# ST_LINK_V2-1_2.net
KiCad netlist of a schematic drawn in Altium Designer
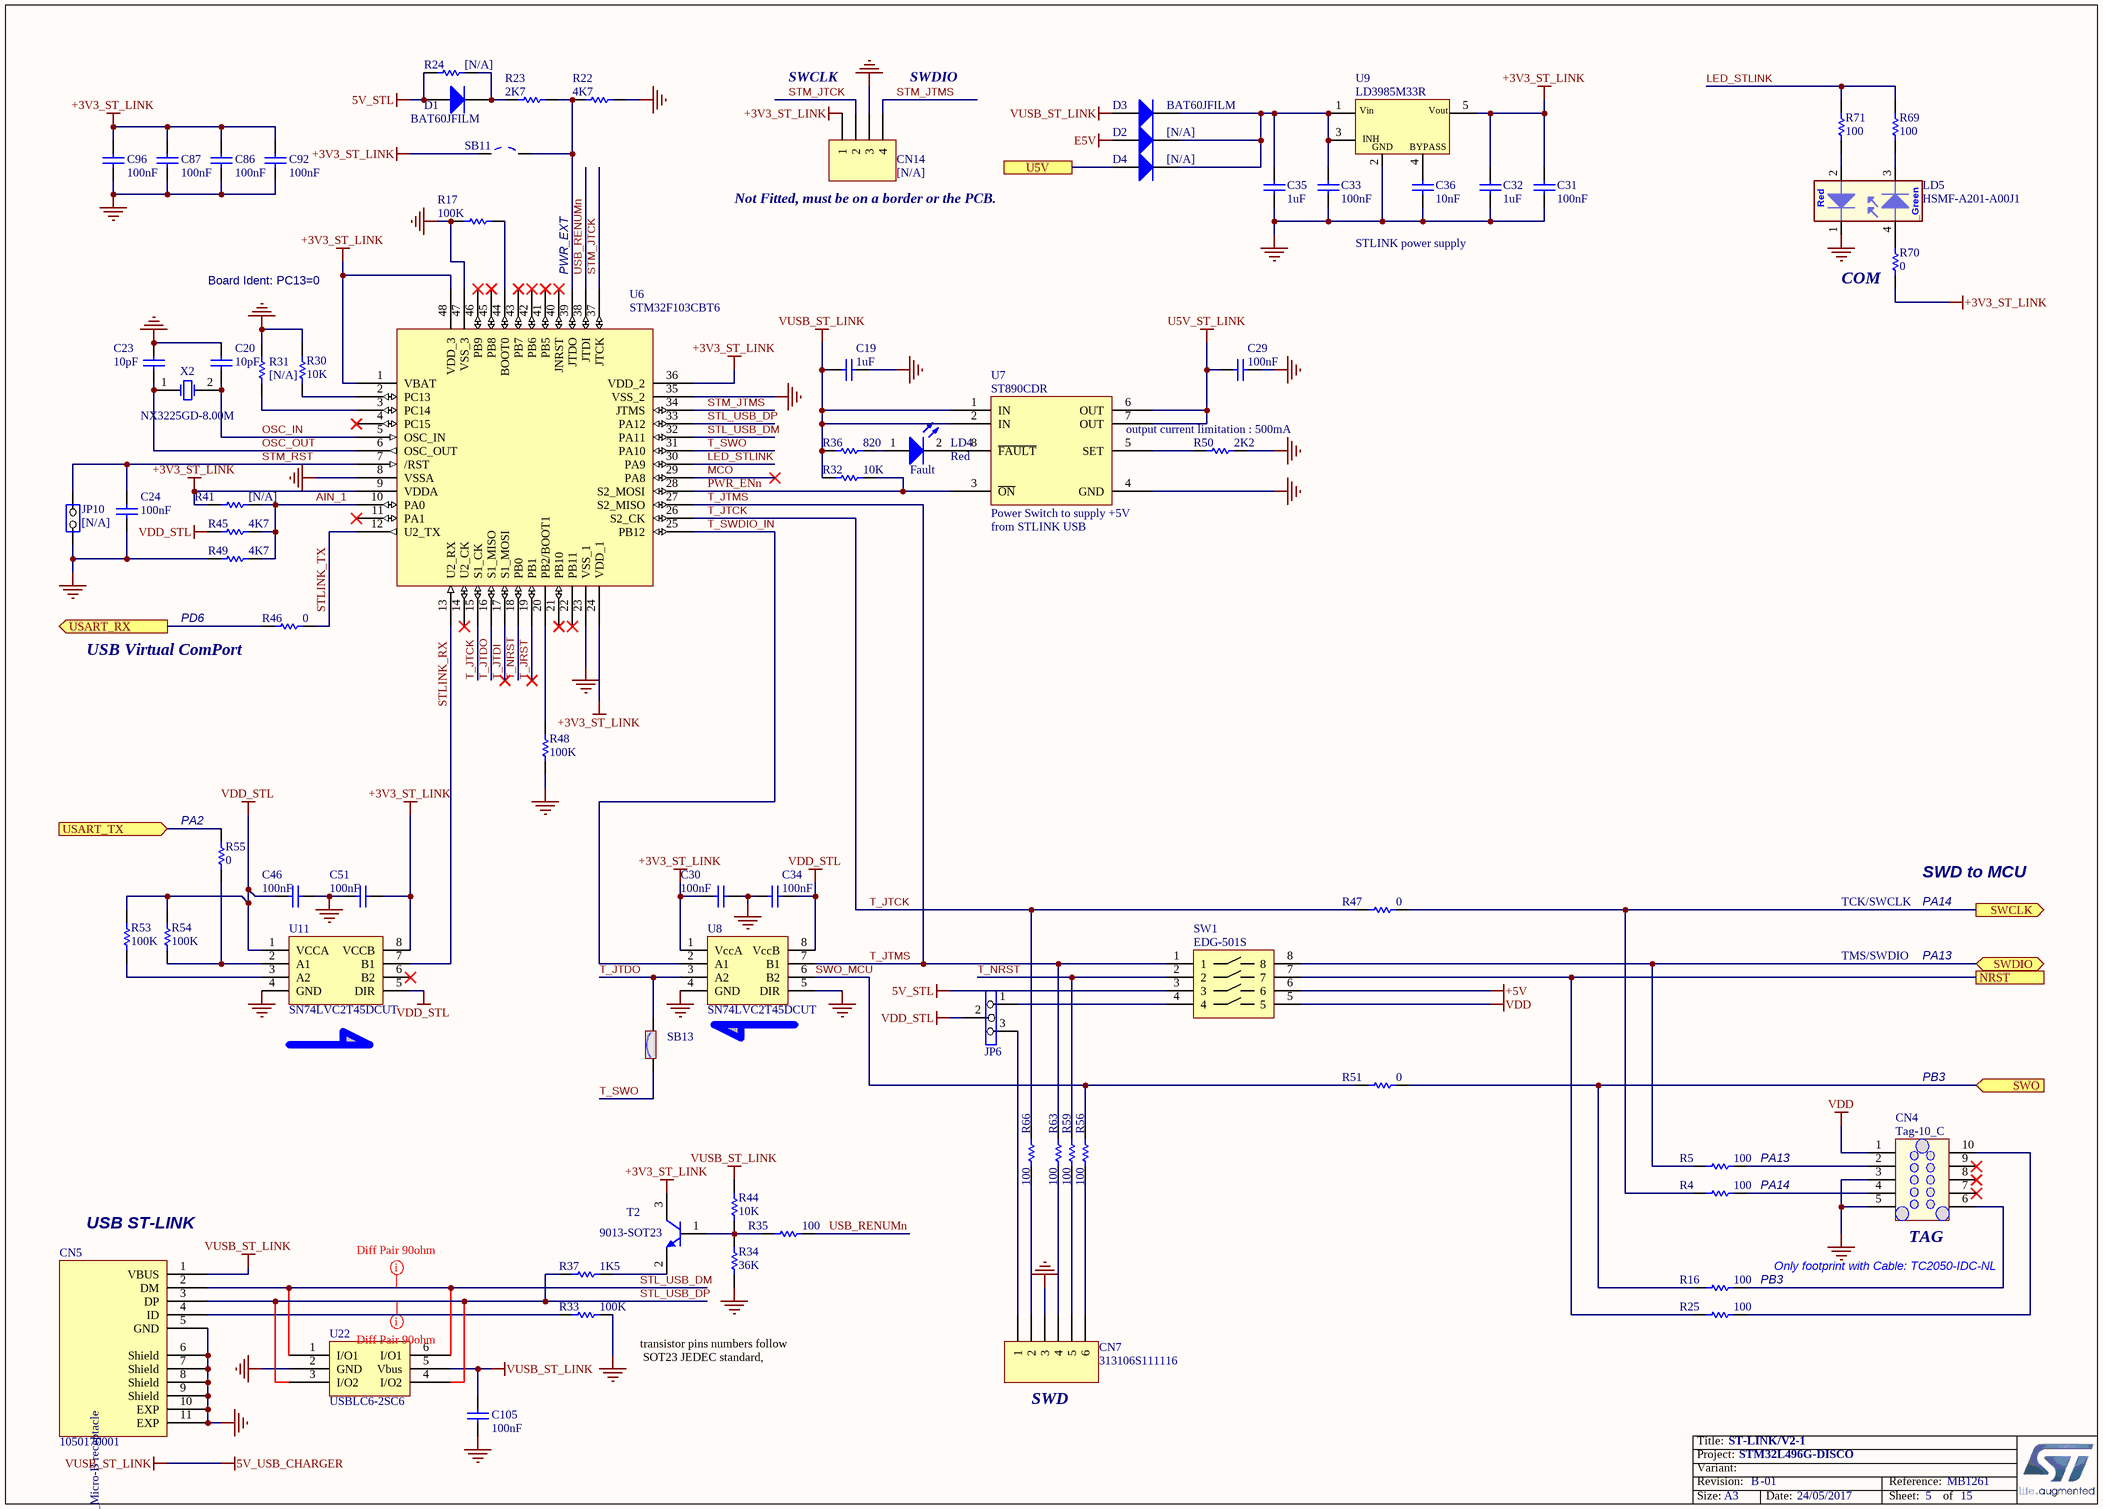
[diagram p0: ST_LINK_V2-1_2.SCHDOC]

(export (version "E")
  (design (tool "Eeschema 10.0.6"))
  (components
    (comp (ref "C19")
      (value "1uF")
      (footprint "0603C")
      (description "Capacitor,1uF,0603,16V,10%,X5R,YAGEO")
      (fields (field (name "Comment") "CC0603KRX5R7BB105") (field (name "PUBLISHER") "Altium Limited"))
      (libsource (lib "Miscellaneous Devices") (part "Cap"))
    )
    (comp (ref "C20")
      (value "10pF")
      (footprint "0603C")
      (description "Capacitor,10pF,5%,50V,NPO,0603,YAGEO")
      (fields (field (name "Comment") "CC0603JRNPO9BN100") (field (name "PUBLISHER") "Altium Limited"))
      (libsource (lib "Miscellaneous Devices") (part "Cap"))
    )
    (comp (ref "C23")
      (value "10pF")
      (footprint "0603C")
      (description "Capacitor,10pF,5%,50V,NPO,0603,YAGEO")
      (fields (field (name "Comment") "CC0603JRNPO9BN100") (field (name "PUBLISHER") "Altium Limited"))
      (libsource (lib "Miscellaneous Devices") (part "Cap"))
    )
    (comp (ref "C24")
      (value "100nF")
      (footprint "0603C")
      (description "Capacitor,100nF,10%,16V,X7R,0603,YAGEO")
      (fields (field (name "Comment") "CC0603KRX7R7BB104") (field (name "PUBLISHER") "Altium Limited"))
      (libsource (lib "Miscellaneous Devices") (part "Cap"))
    )
    (comp (ref "C29")
      (value "100nF")
      (footprint "0603C")
      (description "Capacitor,100nF,10%,16V,X7R,0603,YAGEO")
      (fields (field (name "Comment") "CC0603KRX7R7BB104") (field (name "PUBLISHER") "Altium Limited"))
      (libsource (lib "Miscellaneous Devices") (part "Cap"))
    )
    (comp (ref "C30")
      (value "100nF")
      (footprint "0603C")
      (description "Capacitor,100nF,10%,16V,X7R,0603,YAGEO")
      (fields (field (name "Comment") "CC0603KRX7R7BB104") (field (name "PUBLISHER") "Altium Limited"))
      (libsource (lib "Miscellaneous Devices") (part "Cap"))
    )
    (comp (ref "C31")
      (value "100nF")
      (footprint "0603C")
      (description "Capacitor,100nF,10%,16V,X7R,0603,YAGEO")
      (fields (field (name "Comment") "CC0603KRX7R7BB104") (field (name "PUBLISHER") "Altium Limited"))
      (libsource (lib "Miscellaneous Devices") (part "Cap"))
    )
    (comp (ref "C32")
      (value "1uF")
      (footprint "0603C")
      (description "Capacitor,1uF,0603,16V,10%,X5R,YAGEO")
      (fields (field (name "Comment") "CC0603KRX5R7BB105") (field (name "PUBLISHER") "Altium Limited"))
      (libsource (lib "Miscellaneous Devices") (part "Cap"))
    )
    (comp (ref "C33")
      (value "100nF")
      (footprint "0603C")
      (description "Capacitor,100nF,10%,16V,X7R,0603,YAGEO")
      (fields (field (name "Comment") "CC0603KRX7R7BB104") (field (name "PUBLISHER") "Altium Limited"))
      (libsource (lib "Miscellaneous Devices") (part "Cap"))
    )
    (comp (ref "C34")
      (value "100nF")
      (footprint "0603C")
      (description "Capacitor,100nF,10%,16V,X7R,0603,YAGEO")
      (fields (field (name "Comment") "CC0603KRX7R7BB104") (field (name "PUBLISHER") "Altium Limited"))
      (libsource (lib "Miscellaneous Devices") (part "Cap"))
    )
    (comp (ref "C35")
      (value "1uF")
      (footprint "0603C")
      (description "Capacitor,1uF,0603,16V,10%,X5R,YAGEO")
      (fields (field (name "Comment") "CC0603KRX5R7BB105") (field (name "PUBLISHER") "Altium Limited"))
      (libsource (lib "Miscellaneous Devices") (part "Cap"))
    )
    (comp (ref "C36")
      (value "10nF")
      (footprint "0603C")
      (description "Capacitor,10nF,0603,50V,10%,X7R,YAGEO;")
      (fields (field (name "Comment") "CC0603KRX7R9BB103") (field (name "PUBLISHER") "Altium Limited"))
      (libsource (lib "Miscellaneous Devices") (part "Cap"))
    )
    (comp (ref "C46")
      (value "100nF")
      (footprint "0603C")
      (description "Capacitor,100nF,10%,16V,X7R,0603,YAGEO")
      (fields (field (name "Comment") "CC0603KRX7R7BB104") (field (name "PUBLISHER") "Altium Limited"))
      (libsource (lib "Miscellaneous Devices") (part "Cap"))
    )
    (comp (ref "C51")
      (value "100nF")
      (footprint "0603C")
      (description "Capacitor,100nF,10%,16V,X7R,0603,YAGEO")
      (fields (field (name "Comment") "CC0603KRX7R7BB104") (field (name "PUBLISHER") "Altium Limited"))
      (libsource (lib "Miscellaneous Devices") (part "Cap"))
    )
    (comp (ref "C86")
      (value "100nF")
      (footprint "0603C")
      (description "Capacitor,100nF,10%,16V,X7R,0603,YAGEO")
      (fields (field (name "Comment") "CC0603KRX7R7BB104") (field (name "PUBLISHER") "Altium Limited"))
      (libsource (lib "Miscellaneous Devices") (part "Cap"))
    )
    (comp (ref "C87")
      (value "100nF")
      (footprint "0603C")
      (description "Capacitor,100nF,10%,16V,X7R,0603,YAGEO")
      (fields (field (name "Comment") "CC0603KRX7R7BB104") (field (name "PUBLISHER") "Altium Limited"))
      (libsource (lib "Miscellaneous Devices") (part "Cap"))
    )
    (comp (ref "C92")
      (value "100nF")
      (footprint "0603C")
      (description "Capacitor,100nF,10%,16V,X7R,0603,YAGEO")
      (fields (field (name "Comment") "CC0603KRX7R7BB104") (field (name "PUBLISHER") "Altium Limited"))
      (libsource (lib "Miscellaneous Devices") (part "Cap"))
    )
    (comp (ref "C96")
      (value "100nF")
      (footprint "0603C")
      (description "Capacitor,100nF,10%,16V,X7R,0603,YAGEO")
      (fields (field (name "Comment") "CC0603KRX7R7BB104") (field (name "PUBLISHER") "Altium Limited"))
      (libsource (lib "Miscellaneous Devices") (part "Cap"))
    )
    (comp (ref "C105")
      (value "100nF")
      (footprint "0603C")
      (description "Capacitor,100nF,10%,16V,X7R,0603,YAGEO")
      (fields (field (name "Comment") "CC0603KRX7R7BB104") (field (name "PUBLISHER") "Altium Limited"))
      (libsource (lib "Miscellaneous Devices") (part "Cap"))
    )
    (comp (ref "CN4")
      (value "Tag-10_C")
      (footprint "TC2050-IDC-NL")
      (description "Footprint for TC2050-IDC-430 plug of nails (TM) cable for MP430")
      (libsource (lib "MCD_TOOLS_CONNECTOR") (part "Tag-10_C"))
    )
    (comp (ref "CN5")
      (value "1050170001")
      (footprint "MICRO_USB_B_105017")
      (libsource (lib "Smartphone_accessory") (part "1050170001"))
    )
    (comp (ref "CN7")
      (value "313106S111116")
      (footprint "HDR_1X6_2R54_W")
      (description "Header, 6-Pin")
      (fields (field (name "PUBLISHER") "Altium Limited"))
      (libsource (lib "Miscellaneous Connectors") (part "Header 6"))
    )
    (comp (ref "CN14")
      (value "[N/A]")
      (footprint "HDR_1X4_2R54")
      (description "Header, 4-Pin")
      (fields (field (name "PUBLISHER") "Altium Limited"))
      (libsource (lib "MCD_TOOLS_CONNECTOR") (part "Header 4"))
    )
    (comp (ref "D1")
      (value "BAT60JFILM")
      (footprint "SOD-323")
      (fields (field (name "PROVIDED") "STM"))
      (libsource (lib "MCD_TOOLS") (part "BAT60JFILM"))
    )
    (comp (ref "D2")
      (value "[N/A]")
      (footprint "SOD-323")
      (description "BAT60JFILM")
      (fields (field (name "PROVIDED") "STM"))
      (libsource (lib "MCD_TOOLS") (part "BAT60JFILM"))
    )
    (comp (ref "D3")
      (value "BAT60JFILM")
      (footprint "SOD-323")
      (fields (field (name "PROVIDED") "STM"))
      (libsource (lib "MCD_TOOLS") (part "BAT60JFILM"))
    )
    (comp (ref "D4")
      (value "[N/A]")
      (footprint "SOD-323")
      (description "BAT60JFILM")
      (fields (field (name "PROVIDED") "STM"))
      (libsource (lib "MCD_TOOLS") (part "BAT60JFILM"))
    )
    (comp (ref "JP6")
      (value "3 PIN Jumper")
      (footprint "SIP3")
      (libsource (lib "STR910_SCHLIB") (part "Jumper3"))
    )
    (comp (ref "JP10") (value "[N/A]") (footprint "SIP2") (libsource (lib "*") (part "JP2")))
    (comp (ref "LD4")
      (value "19-217/R6C-AL1M2VY/3T")
      (footprint "0603D")
      (description "LED, Red ,0603")
      (fields
        (field (name "SILKSCREEN") "Fault")
        (field (name "CORLOR") "Red")
        (field (name "PUBLISHER") "Altium Limited")
      )
      (libsource (lib "Miscellaneous Devices") (part "LED2"))
    )
    (comp (ref "LD5")
      (value "HSMF-A201-A00J1")
      (footprint "LED2_3528")
      (description "Bicolor Led")
      (libsource (lib "MCD_TOOLS") (part "LD_BICOLOR_CMS"))
    )
    (comp (ref "R4")
      (value "100")
      (footprint "0603R")
      (description "Resistor, 100 ,0603,1%,YAGEO")
      (fields (field (name "Comment") "RC0603JR-07100RL") (field (name "PUBLISHER") "Altium Limited"))
      (libsource (lib "Miscellaneous Devices") (part "res1"))
    )
    (comp (ref "R5")
      (value "100")
      (footprint "0603R")
      (description "Resistor, 100 ,0603,1%,YAGEO")
      (fields (field (name "Comment") "RC0603JR-07100RL") (field (name "PUBLISHER") "Altium Limited"))
      (libsource (lib "Miscellaneous Devices") (part "res1"))
    )
    (comp (ref "R16")
      (value "100")
      (footprint "0603R")
      (description "Resistor, 100 ,0603,1%,YAGEO")
      (fields (field (name "Comment") "RC0603JR-07100RL") (field (name "PUBLISHER") "Altium Limited"))
      (libsource (lib "Miscellaneous Devices") (part "res1"))
    )
    (comp (ref "R17")
      (value "100K")
      (footprint "0603R")
      (description "Resistor,100K,0603,1%,YAGEO")
      (fields (field (name "Comment") "RC0603FR-07100KL") (field (name "PUBLISHER") "Altium Limited"))
      (libsource (lib "Miscellaneous Devices") (part "res1"))
    )
    (comp (ref "R22")
      (value "4K7")
      (footprint "0603R")
      (description "Resistor,4.7K,0603,1%,YAGEO")
      (fields (field (name "Comment") "RC0603FR-074K7L") (field (name "PUBLISHER") "Altium Limited"))
      (libsource (lib "Miscellaneous Devices") (part "res1"))
    )
    (comp (ref "R23")
      (value "2K7")
      (footprint "0603R")
      (description "Resistor,2.7K,0603,1%,YAGEO")
      (fields (field (name "Comment") "RC0603FR-072K7L") (field (name "PUBLISHER") "Altium Limited"))
      (libsource (lib "Miscellaneous Devices") (part "res1"))
    )
    (comp (ref "R24")
      (value "[N/A]")
      (footprint "0603R")
      (description "Resistor,0,0603,5%,YAGEO")
      (libsource (lib "MCD_TOOLS") (part "Res_0_5%_0402"))
    )
    (comp (ref "R25")
      (value "100")
      (footprint "0603R")
      (description "Resistor, 100 ,0603,1%,YAGEO")
      (fields (field (name "Comment") "RC0603JR-07100RL") (field (name "PUBLISHER") "Altium Limited"))
      (libsource (lib "Miscellaneous Devices") (part "res1"))
    )
    (comp (ref "R30")
      (value "10K")
      (footprint "0603R")
      (description "Resistor,10K,0603,1%,YAGEO")
      (fields (field (name "Comment") "RC0603FR-0710KL") (field (name "PUBLISHER") "Altium Limited"))
      (libsource (lib "Miscellaneous Devices") (part "res1"))
    )
    (comp (ref "R31")
      (value "[N/A]")
      (footprint "0603R")
      (description "Resistor,100K,0603,1%,YAGEO")
      (fields (field (name "PUBLISHER") "Altium Limited"))
      (libsource (lib "Miscellaneous Devices") (part "res1"))
    )
    (comp (ref "R32")
      (value "10K")
      (footprint "0603R")
      (description "Resistor,10K,0603,1%,YAGEO")
      (fields (field (name "Comment") "RC0603FR-0710KL") (field (name "PUBLISHER") "Altium Limited"))
      (libsource (lib "Miscellaneous Devices") (part "res1"))
    )
    (comp (ref "R33")
      (value "100K")
      (footprint "0603R")
      (description "Resistor,100K,0603,1%,YAGEO")
      (fields (field (name "Comment") "RC0603FR-07100KL") (field (name "PUBLISHER") "Altium Limited"))
      (libsource (lib "Miscellaneous Devices") (part "res1"))
    )
    (comp (ref "R34")
      (value "36K")
      (footprint "0603R")
      (description "Resistor,36K,0603,1%,YAGEO")
      (fields (field (name "Comment") "RC0603FR-0736KL") (field (name "PUBLISHER") "Altium Limited"))
      (libsource (lib "Miscellaneous Devices") (part "res1"))
    )
    (comp (ref "R35")
      (value "100")
      (footprint "0603R")
      (description "Resistor, 100 ,0603,1%,YAGEO")
      (fields (field (name "Comment") "RC0603JR-07100RL") (field (name "PUBLISHER") "Altium Limited"))
      (libsource (lib "Miscellaneous Devices") (part "res1"))
    )
    (comp (ref "R36")
      (value "820")
      (footprint "0603R")
      (description "Resistor")
      (fields (field (name "PUBLISHER") "Altium Limited"))
      (libsource (lib "Miscellaneous Devices") (part "res1"))
    )
    (comp (ref "R37")
      (value "1K5")
      (footprint "0603R")
      (description "Resistor,1.5K,0603,1%,YAGEO")
      (fields (field (name "Comment") "RC0603FR-071K5L") (field (name "PUBLISHER") "Altium Limited"))
      (libsource (lib "Miscellaneous Devices") (part "res1"))
    )
    (comp (ref "R41")
      (value "[N/A]")
      (footprint "0603R")
      (description "Resistor,100K,0603,1%,YAGEO")
      (fields (field (name "PUBLISHER") "Altium Limited"))
      (libsource (lib "Miscellaneous Devices") (part "res1"))
    )
    (comp (ref "R44")
      (value "10K")
      (footprint "0603R")
      (description "Resistor,10K,0603,1%,YAGEO")
      (fields (field (name "Comment") "RC0603FR-0710KL") (field (name "PUBLISHER") "Altium Limited"))
      (libsource (lib "Miscellaneous Devices") (part "res1"))
    )
    (comp (ref "R45")
      (value "4K7")
      (footprint "0603R")
      (description "Resistor,4.7K,0603,1%,YAGEO")
      (fields (field (name "Comment") "RC0603FR-074K7L") (field (name "PUBLISHER") "Altium Limited"))
      (libsource (lib "Miscellaneous Devices") (part "res1"))
    )
    (comp (ref "R46")
      (value "0")
      (footprint "0603R")
      (description "Resistor, 0 ,0603,1%,YAGEO")
      (fields (field (name "Comment") "RC0603JR-070RL") (field (name "PUBLISHER") "Altium Limited"))
      (libsource (lib "Miscellaneous Devices") (part "res1"))
    )
    (comp (ref "R47")
      (value "0")
      (footprint "0603R")
      (description "Resistor, 0 ,0603,1%,YAGEO")
      (fields (field (name "Comment") "RC0603JR-070RL") (field (name "PUBLISHER") "Altium Limited"))
      (libsource (lib "Miscellaneous Devices") (part "res1"))
    )
    (comp (ref "R48")
      (value "100K")
      (footprint "0603R")
      (description "Resistor,100K,0603,1%,YAGEO")
      (fields (field (name "Comment") "RC0603FR-07100KL") (field (name "PUBLISHER") "Altium Limited"))
      (libsource (lib "Miscellaneous Devices") (part "res1"))
    )
    (comp (ref "R49")
      (value "4K7")
      (footprint "0603R")
      (description "Resistor,4.7K,0603,1%,YAGEO")
      (fields (field (name "Comment") "RC0603FR-074K7L") (field (name "PUBLISHER") "Altium Limited"))
      (libsource (lib "Miscellaneous Devices") (part "res1"))
    )
    (comp (ref "R50")
      (value "2K2")
      (footprint "0603R")
      (description "Resistor,2.2K,0603,1%,YAGEO")
      (fields (field (name "Comment") "RC0603FR-072K2L") (field (name "PUBLISHER") "Altium Limited"))
      (libsource (lib "Miscellaneous Devices") (part "res1"))
    )
    (comp (ref "R51")
      (value "0")
      (footprint "0603R")
      (description "Resistor, 0 ,0603,1%,YAGEO")
      (fields (field (name "Comment") "RC0603JR-070RL") (field (name "PUBLISHER") "Altium Limited"))
      (libsource (lib "Miscellaneous Devices") (part "res1"))
    )
    (comp (ref "R53")
      (value "100K")
      (footprint "0603R")
      (description "Resistor,100K,0603,1%,YAGEO")
      (fields (field (name "Comment") "RC0603FR-07100KL") (field (name "PUBLISHER") "Altium Limited"))
      (libsource (lib "Miscellaneous Devices") (part "res1"))
    )
    (comp (ref "R54")
      (value "100K")
      (footprint "0603R")
      (description "Resistor,100K,0603,1%,YAGEO")
      (fields (field (name "Comment") "RC0603FR-07100KL") (field (name "PUBLISHER") "Altium Limited"))
      (libsource (lib "Miscellaneous Devices") (part "res1"))
    )
    (comp (ref "R55")
      (value "0")
      (footprint "0603R")
      (description "Resistor, 0 ,0603,1%,YAGEO")
      (fields (field (name "Comment") "RC0603JR-070RL") (field (name "PUBLISHER") "Altium Limited"))
      (libsource (lib "Miscellaneous Devices") (part "res1"))
    )
    (comp (ref "R56")
      (value "100")
      (footprint "0603R")
      (description "Resistor, 100 ,0603,1%,YAGEO")
      (fields (field (name "Comment") "RC0603JR-07100RL") (field (name "PUBLISHER") "Altium Limited"))
      (libsource (lib "Miscellaneous Devices") (part "res1"))
    )
    (comp (ref "R59")
      (value "100")
      (footprint "0603R")
      (description "Resistor, 100 ,0603,1%,YAGEO")
      (fields (field (name "Comment") "RC0603JR-07100RL") (field (name "PUBLISHER") "Altium Limited"))
      (libsource (lib "Miscellaneous Devices") (part "res1"))
    )
    (comp (ref "R63")
      (value "100")
      (footprint "0603R")
      (description "Resistor, 100 ,0603,1%,YAGEO")
      (fields (field (name "Comment") "RC0603JR-07100RL") (field (name "PUBLISHER") "Altium Limited"))
      (libsource (lib "Miscellaneous Devices") (part "res1"))
    )
    (comp (ref "R66")
      (value "100")
      (footprint "0603R")
      (description "Resistor, 100 ,0603,1%,YAGEO")
      (fields (field (name "Comment") "RC0603JR-07100RL") (field (name "PUBLISHER") "Altium Limited"))
      (libsource (lib "Miscellaneous Devices") (part "res1"))
    )
    (comp (ref "R69")
      (value "100")
      (footprint "0603R")
      (description "Resistor, 100 ,0603,1%,YAGEO")
      (fields (field (name "Comment") "RC0603JR-07100RL") (field (name "PUBLISHER") "Altium Limited"))
      (libsource (lib "Miscellaneous Devices") (part "res1"))
    )
    (comp (ref "R70")
      (value "0")
      (footprint "0603R")
      (description "Resistor, 0 ,0603,1%,YAGEO")
      (fields (field (name "Comment") "RC0603JR-070RL") (field (name "PUBLISHER") "Altium Limited"))
      (libsource (lib "Miscellaneous Devices") (part "res1"))
    )
    (comp (ref "R71")
      (value "100")
      (footprint "0603R")
      (description "Resistor, 100 ,0603,1%,YAGEO")
      (fields (field (name "Comment") "RC0603JR-07100RL") (field (name "PUBLISHER") "Altium Limited"))
      (libsource (lib "Miscellaneous Devices") (part "res1"))
    )
    (comp (ref "SB11")
      (value "Solder Bridge OFF")
      (footprint "SB_0603")
      (libsource (lib "MCD_TOOLS") (part "SB_OFF"))
    )
    (comp (ref "SB13")
      (value "Solder Bridge ON")
      (footprint "SB_0603")
      (libsource (lib "MCD_TOOLS") (part "SB_ON"))
    )
    (comp (ref "SW1")
      (value "EDG-501S")
      (footprint "SW1_11R7X9R7-12R2X9R65-HDR_CPT")
      (description "Gold Plated Contacts,4PST,1x4 Switch")
      (libsource (lib "Big Orga") (part "EDG-501S"))
    )
    (comp (ref "T2")
      (value "9013-SOT23")
      (footprint "SOT-23")
      (description "NPN Bipolar Transistor")
      (fields (field (name "PUBLISHER") "Altium Limited"))
      (libsource (lib "MB1167") (part "NPN"))
    )
    (comp (ref "U6")
      (value "STM32F103CBT6")
      (footprint "LQFP48_0R5_9X9")
      (description "IC,STM32F103CBT6,LQFP-48")
      (libsource (lib "*") (part "STM32F10x(48pin)"))
    )
    (comp (ref "U7")
      (value "ST890CDR")
      (footprint "SOIC8_1R27_4R9X6")
      (libsource (lib "MB1219") (part "ST890CDR"))
    )
    (comp (ref "U8")
      (value "SN74LVC2T45DCUT")
      (footprint "USOP8_0R5_2X3R1")
      (libsource (lib "STLINK") (part "SN74LVC2T45DCUT"))
    )
    (comp (ref "U9")
      (value "LD3985M33R")
      (footprint "SOT23-5")
      (description "Ultra low drop-low noise BiCMOS voltage, regulators low ESR capacitors compatible")
      (fields (field (name "PROVIDED") "STM"))
      (libsource (lib "MCD_TOOLS") (part "LD3985M33R"))
    )
    (comp (ref "U11")
      (value "SN74LVC2T45DCUT")
      (footprint "USOP8_0R5_2X3R1")
      (libsource (lib "MB818") (part "SN74LVC2T45DCUT"))
    )
    (comp (ref "U22")
      (value "USBLC6-2SC6")
      (footprint "SOT23-6L")
      (libsource (lib "MB1137") (part "USBLC6-2SC6"))
    )
    (comp (ref "X2")
      (value "NX3225GD-8.00M")
      (footprint "XTAL_2SM_3R2X2R5")
      (description "Crystal 8Mhz, 8pF, -+50PPM, SMD")
      (libsource (lib "MCD_TOOLS") (part "XTAL_8M_NX3225GD"))
    )
  )
  (nets
    (net (code "1") (name "+3V3_ST_LINK") (class "Default")
      (node (ref "C30") (pin "2") (pinfunction "2_2") (pintype "passive"))
      (node (ref "C31") (pin "1") (pinfunction "1_1") (pintype "passive"))
      (node (ref "C32") (pin "1") (pinfunction "1_1") (pintype "passive"))
      (node (ref "C51") (pin "2") (pinfunction "2_2") (pintype "passive"))
      (node (ref "C86") (pin "1") (pinfunction "1_1") (pintype "passive"))
      (node (ref "C87") (pin "1") (pinfunction "1_1") (pintype "passive"))
      (node (ref "C92") (pin "1") (pinfunction "1_1") (pintype "passive"))
      (node (ref "C96") (pin "1") (pinfunction "1_1") (pintype "passive"))
      (node (ref "CN14") (pin "1") (pinfunction "1_1") (pintype "passive"))
      (node (ref "R41") (pin "1") (pinfunction "1_1") (pintype "passive"))
      (node (ref "R70") (pin "1") (pinfunction "1_1") (pintype "passive"))
      (node (ref "SB11") (pin "1") (pinfunction "1_1") (pintype "passive"))
      (node (ref "T2") (pin "3") (pinfunction "C_3") (pintype "passive"))
      (node (ref "U11") (pin "8") (pinfunction "VCCB_8") (pintype "passive"))
      (node (ref "U6") (pin "1") (pinfunction "VBAT_1") (pintype "power_in"))
      (node (ref "U6") (pin "24") (pinfunction "VDD_1_24") (pintype "power_in"))
      (node (ref "U6") (pin "36") (pinfunction "VDD_2_36") (pintype "power_in"))
      (node (ref "U6") (pin "48") (pinfunction "VDD_3_48") (pintype "power_in"))
      (node (ref "U6") (pin "9") (pinfunction "VDDA_9") (pintype "power_in"))
      (node (ref "U8") (pin "1") (pinfunction "VccA_1") (pintype "passive"))
      (node (ref "U9") (pin "5") (pinfunction "Vout_5") (pintype "passive"))
    )
    (net (code "2") (name "+5V") (class "Default")
      (node (ref "SW1") (pin "6") (pinfunction "6_6") (pintype "passive"))
    )
    (net (code "3") (name "/AIN_1") (class "Default")
      (node (ref "R41") (pin "2") (pinfunction "2_2") (pintype "passive"))
      (node (ref "R45") (pin "1") (pinfunction "1_1") (pintype "passive"))
      (node (ref "R49") (pin "1") (pinfunction "1_1") (pintype "passive"))
      (node (ref "U6") (pin "10") (pinfunction "PA0_10") (pintype "bidirectional"))
    )
    (net (code "4") (name "/LED_STLINK") (class "Default")
      (node (ref "R69") (pin "1") (pinfunction "1_1") (pintype "passive"))
      (node (ref "R71") (pin "1") (pinfunction "1_1") (pintype "passive"))
      (node (ref "U6") (pin "30") (pinfunction "PA9_30") (pintype "bidirectional"))
    )
    (net (code "5") (name "/MCO") (class "Default")
      (node (ref "U6") (pin "29") (pinfunction "PA8_29") (pintype "bidirectional+no_connect"))
    )
    (net (code "6") (name "/NRST") (class "Default")
      (node (ref "R25") (pin "2") (pinfunction "2_2") (pintype "passive"))
      (node (ref "SW1") (pin "7") (pinfunction "7_7") (pintype "passive"))
    )
    (net (code "7") (name "/OSC_IN") (class "Default")
      (node (ref "C20") (pin "2") (pinfunction "2_2") (pintype "passive"))
      (node (ref "U6") (pin "5") (pinfunction "OSC_IN_5") (pintype "input"))
      (node (ref "X2") (pin "2") (pinfunction "OSC2_2") (pintype "passive"))
    )
    (net (code "8") (name "/OSC_OUT") (class "Default")
      (node (ref "C23") (pin "2") (pinfunction "2_2") (pintype "passive"))
      (node (ref "U6") (pin "6") (pinfunction "OSC_OUT_6") (pintype "output"))
      (node (ref "X2") (pin "1") (pinfunction "OSC1_1") (pintype "passive"))
    )
    (net (code "9") (name "/PWR_ENn") (class "Default")
      (node (ref "R32") (pin "2") (pinfunction "2_2") (pintype "passive"))
      (node (ref "U6") (pin "28") (pinfunction "S2_MOSI_28") (pintype "bidirectional"))
      (node (ref "U7") (pin "3") (pinfunction "~{ON}_3") (pintype "passive"))
    )
    (net (code "10") (name "/STLINK_RX") (class "Default")
      (node (ref "U11") (pin "7") (pinfunction "B1_7") (pintype "passive"))
      (node (ref "U6") (pin "13") (pinfunction "U2_RX_13") (pintype "input"))
    )
    (net (code "11") (name "/STLINK_TX") (class "Default")
      (node (ref "R46") (pin "1") (pinfunction "1_1") (pintype "passive"))
      (node (ref "U6") (pin "12") (pinfunction "U2_TX_12") (pintype "output"))
    )
    (net (code "12") (name "/STL_USB_DM") (class "Default")
      (node (ref "CN5") (pin "2") (pinfunction "DM_2") (pintype "passive"))
      (node (ref "U22") (pin "1") (pinfunction "I/O1_1") (pintype "passive"))
      (node (ref "U22") (pin "6") (pinfunction "I/O1_6") (pintype "passive"))
      (node (ref "U6") (pin "32") (pinfunction "PA11_32") (pintype "bidirectional"))
    )
    (net (code "13") (name "/STL_USB_DP") (class "Default")
      (node (ref "CN5") (pin "3") (pinfunction "DP_3") (pintype "passive"))
      (node (ref "R37") (pin "2") (pinfunction "2_2") (pintype "passive"))
      (node (ref "U22") (pin "3") (pinfunction "I/O2_3") (pintype "passive"))
      (node (ref "U22") (pin "4") (pinfunction "I/O2_4") (pintype "passive"))
      (node (ref "U6") (pin "33") (pinfunction "PA12_33") (pintype "bidirectional"))
    )
    (net (code "14") (name "/STM_JTCK") (class "Default")
      (node (ref "CN14") (pin "2") (pinfunction "2_2") (pintype "passive"))
      (node (ref "U6") (pin "37") (pinfunction "JTCK_37") (pintype "bidirectional"))
    )
    (net (code "15") (name "/STM_JTMS") (class "Default")
      (node (ref "CN14") (pin "4") (pinfunction "4_4") (pintype "passive"))
      (node (ref "U6") (pin "34") (pinfunction "JTMS_34") (pintype "bidirectional"))
    )
    (net (code "16") (name "/STM_RST") (class "Default")
      (node (ref "C24") (pin "1") (pinfunction "1_1") (pintype "passive"))
      (node (ref "JP10") (pin "1") (pinfunction "COMMON_1") (pintype "passive"))
      (node (ref "U6") (pin "7") (pinfunction "/RST_7") (pintype "input"))
    )
    (net (code "17") (name "/SWCLK") (class "Default")
      (node (ref "R4") (pin "2") (pinfunction "2_2") (pintype "passive"))
      (node (ref "R47") (pin "1") (pinfunction "1_1") (pintype "passive"))
    )
    (net (code "18") (name "/SWDIO") (class "Default")
      (node (ref "R5") (pin "2") (pinfunction "2_2") (pintype "passive"))
      (node (ref "SW1") (pin "8") (pinfunction "8_8") (pintype "passive"))
    )
    (net (code "19") (name "/SWO") (class "Default")
      (node (ref "R16") (pin "2") (pinfunction "2_2") (pintype "passive"))
      (node (ref "R51") (pin "1") (pinfunction "1_1") (pintype "passive"))
    )
    (net (code "20") (name "/SWO_MCU") (class "Default")
      (node (ref "R51") (pin "2") (pinfunction "2_2") (pintype "passive"))
      (node (ref "R56") (pin "2") (pinfunction "2_2") (pintype "passive"))
      (node (ref "U8") (pin "6") (pinfunction "B2_6") (pintype "passive"))
    )
    (net (code "21") (name "/T_JRST") (class "Default")
      (node (ref "U6") (pin "19") (pinfunction "PB1_19") (pintype "bidirectional+no_connect"))
    )
    (net (code "22") (name "/T_JTCK") (class "Default")
      (node (ref "R47") (pin "2") (pinfunction "2_2") (pintype "passive"))
      (node (ref "R66") (pin "2") (pinfunction "2_2") (pintype "passive"))
      (node (ref "U6") (pin "15") (pinfunction "S1_CK_15") (pintype "bidirectional"))
      (node (ref "U6") (pin "26") (pinfunction "S2_CK_26") (pintype "bidirectional"))
    )
    (net (code "23") (name "/T_JTDI") (class "Default")
      (node (ref "U6") (pin "17") (pinfunction "S1_MOSI_17") (pintype "bidirectional+no_connect"))
    )
    (net (code "24") (name "/T_JTDO") (class "Default")
      (node (ref "SB13") (pin "2") (pinfunction "2_2") (pintype "passive"))
      (node (ref "U6") (pin "16") (pinfunction "S1_MISO_16") (pintype "bidirectional"))
      (node (ref "U8") (pin "3") (pinfunction "A2_3") (pintype "passive"))
    )
    (net (code "25") (name "/T_JTMS") (class "Default")
      (node (ref "R63") (pin "2") (pinfunction "2_2") (pintype "passive"))
      (node (ref "SW1") (pin "1") (pinfunction "1_1") (pintype "passive"))
      (node (ref "U6") (pin "27") (pinfunction "S2_MISO_27") (pintype "bidirectional"))
      (node (ref "U8") (pin "7") (pinfunction "B1_7") (pintype "passive"))
    )
    (net (code "26") (name "/T_NRST") (class "Default")
      (node (ref "R59") (pin "2") (pinfunction "2_2") (pintype "passive"))
      (node (ref "SW1") (pin "2") (pinfunction "2_2") (pintype "passive"))
      (node (ref "U6") (pin "18") (pinfunction "PB0_18") (pintype "bidirectional"))
    )
    (net (code "27") (name "/T_SWDIO_IN") (class "Default")
      (node (ref "U6") (pin "25") (pinfunction "PB12_25") (pintype "bidirectional"))
      (node (ref "U8") (pin "2") (pinfunction "A1_2") (pintype "passive"))
    )
    (net (code "28") (name "/T_SWO") (class "Default")
      (node (ref "SB13") (pin "1") (pinfunction "1_1") (pintype "passive"))
      (node (ref "U6") (pin "31") (pinfunction "PA10_31") (pintype "bidirectional"))
    )
    (net (code "29") (name "/U5V") (class "Default")
      (node (ref "D4") (pin "1") (pinfunction "A_1") (pintype "passive"))
    )
    (net (code "30") (name "/USART_RX") (class "Default")
      (node (ref "R46") (pin "2") (pinfunction "2_2") (pintype "passive"))
    )
    (net (code "31") (name "/USART_TX") (class "Default")
      (node (ref "R55") (pin "1") (pinfunction "1_1") (pintype "passive"))
    )
    (net (code "32") (name "/USB_RENUMn") (class "Default")
      (node (ref "R35") (pin "2") (pinfunction "2_2") (pintype "passive"))
      (node (ref "U6") (pin "38") (pinfunction "JTDI_38") (pintype "bidirectional"))
    )
    (net (code "33") (name "5V_STL") (class "Default")
      (node (ref "D1") (pin "1") (pinfunction "A_1") (pintype "passive"))
      (node (ref "R24") (pin "2") (pinfunction "2_2") (pintype "passive"))
      (node (ref "SW1") (pin "3") (pinfunction "3_3") (pintype "passive"))
    )
    (net (code "34") (name "5V_USB_CHARGER") (class "Default")
      (node (ref "C105") (pin "1") (pinfunction "1_1") (pintype "passive"))
      (node (ref "C19") (pin "2") (pinfunction "2_2") (pintype "passive"))
      (node (ref "CN5") (pin "1") (pinfunction "VBUS_1") (pintype "passive"))
      (node (ref "D3") (pin "1") (pinfunction "A_1") (pintype "passive"))
      (node (ref "R32") (pin "1") (pinfunction "1_1") (pintype "passive"))
      (node (ref "R36") (pin "2") (pinfunction "2_2") (pintype "passive"))
      (node (ref "R44") (pin "1") (pinfunction "1_1") (pintype "passive"))
      (node (ref "U22") (pin "5") (pinfunction "Vbus_5") (pintype "passive"))
      (node (ref "U7") (pin "1") (pinfunction "IN_1") (pintype "passive"))
      (node (ref "U7") (pin "2") (pinfunction "IN_2") (pintype "passive"))
    )
    (net (code "35") (name "E5V") (class "Default")
      (node (ref "D2") (pin "1") (pinfunction "A_1") (pintype "passive"))
    )
    (net (code "36") (name "GND") (class "Default")
      (node (ref "C105") (pin "2") (pinfunction "2_2") (pintype "passive"))
      (node (ref "C19") (pin "1") (pinfunction "1_1") (pintype "passive"))
      (node (ref "C20") (pin "1") (pinfunction "1_1") (pintype "passive"))
      (node (ref "C23") (pin "1") (pinfunction "1_1") (pintype "passive"))
      (node (ref "C24") (pin "2") (pinfunction "2_2") (pintype "passive"))
      (node (ref "C29") (pin "1") (pinfunction "1_1") (pintype "passive"))
      (node (ref "C30") (pin "1") (pinfunction "1_1") (pintype "passive"))
      (node (ref "C31") (pin "2") (pinfunction "2_2") (pintype "passive"))
      (node (ref "C32") (pin "2") (pinfunction "2_2") (pintype "passive"))
      (node (ref "C33") (pin "2") (pinfunction "2_2") (pintype "passive"))
      (node (ref "C34") (pin "2") (pinfunction "2_2") (pintype "passive"))
      (node (ref "C35") (pin "2") (pinfunction "2_2") (pintype "passive"))
      (node (ref "C36") (pin "2") (pinfunction "2_2") (pintype "passive"))
      (node (ref "C46") (pin "2") (pinfunction "2_2") (pintype "passive"))
      (node (ref "C51") (pin "1") (pinfunction "1_1") (pintype "passive"))
      (node (ref "C86") (pin "2") (pinfunction "2_2") (pintype "passive"))
      (node (ref "C87") (pin "2") (pinfunction "2_2") (pintype "passive"))
      (node (ref "C92") (pin "2") (pinfunction "2_2") (pintype "passive"))
      (node (ref "C96") (pin "2") (pinfunction "2_2") (pintype "passive"))
      (node (ref "CN14") (pin "3") (pinfunction "3_3") (pintype "passive"))
      (node (ref "CN4") (pin "3") (pinfunction "3_3") (pintype "passive"))
      (node (ref "CN4") (pin "5") (pinfunction "5_5") (pintype "passive"))
      (node (ref "CN5") (pin "10") (pinfunction "EXP_10") (pintype "passive"))
      (node (ref "CN5") (pin "11") (pinfunction "EXP_11") (pintype "passive"))
      (node (ref "CN5") (pin "5") (pinfunction "GND_5") (pintype "passive"))
      (node (ref "CN5") (pin "6") (pinfunction "Shield_6") (pintype "passive"))
      (node (ref "CN5") (pin "7") (pinfunction "Shield_7") (pintype "passive"))
      (node (ref "CN5") (pin "8") (pinfunction "Shield_8") (pintype "passive"))
      (node (ref "CN5") (pin "9") (pinfunction "Shield_9") (pintype "passive"))
      (node (ref "CN7") (pin "3") (pinfunction "3_3") (pintype "passive"))
      (node (ref "JP10") (pin "2") (pinfunction "NO_2") (pintype "passive"))
      (node (ref "LD5") (pin "1") (pinfunction "1_1") (pintype "passive"))
      (node (ref "R17") (pin "2") (pinfunction "2_2") (pintype "passive"))
      (node (ref "R22") (pin "1") (pinfunction "1_1") (pintype "passive"))
      (node (ref "R30") (pin "1") (pinfunction "1_1") (pintype "passive"))
      (node (ref "R31") (pin "1") (pinfunction "1_1") (pintype "passive"))
      (node (ref "R33") (pin "1") (pinfunction "1_1") (pintype "passive"))
      (node (ref "R34") (pin "2") (pinfunction "2_2") (pintype "passive"))
      (node (ref "R48") (pin "1") (pinfunction "1_1") (pintype "passive"))
      (node (ref "R49") (pin "2") (pinfunction "2_2") (pintype "passive"))
      (node (ref "R50") (pin "1") (pinfunction "1_1") (pintype "passive"))
      (node (ref "U11") (pin "4") (pinfunction "GND_4") (pintype "passive"))
      (node (ref "U22") (pin "2") (pinfunction "GND_2") (pintype "passive"))
      (node (ref "U6") (pin "23") (pinfunction "VSS_1_23") (pintype "passive"))
      (node (ref "U6") (pin "35") (pinfunction "VSS_2_35") (pintype "passive"))
      (node (ref "U6") (pin "47") (pinfunction "VSS_3_47") (pintype "passive"))
      (node (ref "U6") (pin "8") (pinfunction "VSSA_8") (pintype "passive"))
      (node (ref "U7") (pin "4") (pinfunction "GND_4") (pintype "passive"))
      (node (ref "U8") (pin "4") (pinfunction "GND_4") (pintype "passive"))
      (node (ref "U8") (pin "5") (pinfunction "DIR_5") (pintype "passive"))
      (node (ref "U9") (pin "2") (pinfunction "GND_2") (pintype "passive"))
    )
    (net (code "37") (name "Net-(CN4-Pad2)") (class "Default")
      (node (ref "CN4") (pin "2") (pinfunction "2_2") (pintype "passive"))
      (node (ref "R5") (pin "1") (pinfunction "1_1") (pintype "passive"))
    )
    (net (code "38") (name "Net-(CN4-Pad4)") (class "Default")
      (node (ref "CN4") (pin "4") (pinfunction "4_4") (pintype "passive"))
      (node (ref "R4") (pin "1") (pinfunction "1_1") (pintype "passive"))
    )
    (net (code "39") (name "Net-(CN4-Pad6)") (class "Default")
      (node (ref "CN4") (pin "6") (pinfunction "6_6") (pintype "passive"))
      (node (ref "R16") (pin "1") (pinfunction "1_1") (pintype "passive"))
    )
    (net (code "40") (name "Net-(CN4-Pad10)") (class "Default")
      (node (ref "CN4") (pin "10") (pinfunction "10_10") (pintype "passive"))
      (node (ref "R25") (pin "1") (pinfunction "1_1") (pintype "passive"))
    )
    (net (code "41") (name "Net-(CN5-ID)") (class "Default")
      (node (ref "CN5") (pin "4") (pinfunction "ID_4") (pintype "passive"))
      (node (ref "R33") (pin "2") (pinfunction "2_2") (pintype "passive"))
    )
    (net (code "42") (name "Net-(CN7-Pad1)") (class "Default")
      (node (ref "CN7") (pin "1") (pinfunction "1_1") (pintype "passive"))
      (node (ref "JP6") (pin "3") (pintype "passive"))
    )
    (net (code "43") (name "Net-(CN7-Pad2)") (class "Default")
      (node (ref "CN7") (pin "2") (pinfunction "2_2") (pintype "passive"))
      (node (ref "R66") (pin "1") (pinfunction "1_1") (pintype "passive"))
    )
    (net (code "44") (name "Net-(CN7-Pad4)") (class "Default")
      (node (ref "CN7") (pin "4") (pinfunction "4_4") (pintype "passive"))
      (node (ref "R63") (pin "1") (pinfunction "1_1") (pintype "passive"))
    )
    (net (code "45") (name "Net-(CN7-Pad5)") (class "Default")
      (node (ref "CN7") (pin "5") (pinfunction "5_5") (pintype "passive"))
      (node (ref "R59") (pin "1") (pinfunction "1_1") (pintype "passive"))
    )
    (net (code "46") (name "Net-(CN7-Pad6)") (class "Default")
      (node (ref "CN7") (pin "6") (pinfunction "6_6") (pintype "passive"))
      (node (ref "R56") (pin "1") (pinfunction "1_1") (pintype "passive"))
    )
    (net (code "47") (name "Net-(D1-K)") (class "Default")
      (node (ref "D1") (pin "2") (pinfunction "K_2") (pintype "passive"))
      (node (ref "R23") (pin "2") (pinfunction "2_2") (pintype "passive"))
      (node (ref "R24") (pin "1") (pinfunction "1_1") (pintype "passive"))
    )
    (net (code "48") (name "Net-(D2-K)") (class "Default")
      (node (ref "C33") (pin "1") (pinfunction "1_1") (pintype "passive"))
      (node (ref "C35") (pin "1") (pinfunction "1_1") (pintype "passive"))
      (node (ref "D2") (pin "2") (pinfunction "K_2") (pintype "passive"))
      (node (ref "D3") (pin "2") (pinfunction "K_2") (pintype "passive"))
      (node (ref "D4") (pin "2") (pinfunction "K_2") (pintype "passive"))
      (node (ref "U9") (pin "1") (pinfunction "Vin_1") (pintype "passive"))
      (node (ref "U9") (pin "3") (pinfunction "CE_3") (pintype "passive"))
    )
    (net (code "49") (name "Net-(JP6-Pad1)") (class "Default")
      (node (ref "JP6") (pin "1") (pintype "passive"))
      (node (ref "SW1") (pin "4") (pinfunction "4_4") (pintype "passive"))
    )
    (net (code "50") (name "Net-(LD4-A)") (class "Default")
      (node (ref "LD4") (pin "1") (pinfunction "A_1") (pintype "passive"))
      (node (ref "R36") (pin "1") (pinfunction "1_1") (pintype "passive"))
    )
    (net (code "51") (name "Net-(LD4-K)") (class "Default")
      (node (ref "LD4") (pin "2") (pinfunction "K_2") (pintype "passive"))
      (node (ref "U7") (pin "8") (pinfunction "~{FAULT}_8") (pintype "passive"))
    )
    (net (code "52") (name "Net-(LD5-Pad2)") (class "Default")
      (node (ref "LD5") (pin "2") (pinfunction "2_2") (pintype "passive"))
      (node (ref "R71") (pin "2") (pinfunction "2_2") (pintype "passive"))
    )
    (net (code "53") (name "Net-(LD5-Pad3)") (class "Default")
      (node (ref "LD5") (pin "3") (pinfunction "3_3") (pintype "passive"))
      (node (ref "R69") (pin "2") (pinfunction "2_2") (pintype "passive"))
    )
    (net (code "54") (name "Net-(LD5-Pad4)") (class "Default")
      (node (ref "LD5") (pin "4") (pinfunction "4_4") (pintype "passive"))
      (node (ref "R70") (pin "2") (pinfunction "2_2") (pintype "passive"))
    )
    (net (code "55") (name "Net-(T2-B)") (class "Default")
      (node (ref "R34") (pin "1") (pinfunction "1_1") (pintype "passive"))
      (node (ref "R35") (pin "1") (pinfunction "1_1") (pintype "passive"))
      (node (ref "R44") (pin "2") (pinfunction "2_2") (pintype "passive"))
      (node (ref "T2") (pin "1") (pinfunction "B_1") (pintype "passive"))
    )
    (net (code "56") (name "Net-(T2-E)") (class "Default")
      (node (ref "R37") (pin "1") (pinfunction "1_1") (pintype "passive"))
      (node (ref "T2") (pin "2") (pinfunction "E_2") (pintype "passive"))
    )
    (net (code "57") (name "Net-(U6-BOOT0)") (class "Default")
      (node (ref "R17") (pin "1") (pinfunction "1_1") (pintype "passive"))
      (node (ref "U6") (pin "44") (pinfunction "BOOT0_44") (pintype "bidirectional"))
    )
    (net (code "58") (name "Net-(U6-JTDO)") (class "Default")
      (node (ref "R22") (pin "2") (pinfunction "2_2") (pintype "passive"))
      (node (ref "R23") (pin "1") (pinfunction "1_1") (pintype "passive"))
      (node (ref "SB11") (pin "2") (pinfunction "2_2") (pintype "passive"))
      (node (ref "U6") (pin "39") (pinfunction "JTDO_39") (pintype "bidirectional"))
    )
    (net (code "59") (name "Net-(U6-PB2{slash}BOOT1)") (class "Default")
      (node (ref "R48") (pin "2") (pinfunction "2_2") (pintype "passive"))
      (node (ref "U6") (pin "20") (pinfunction "PB2/BOOT1_20") (pintype "passive"))
    )
    (net (code "60") (name "Net-(U6-PC13)") (class "Default")
      (node (ref "R30") (pin "2") (pinfunction "2_2") (pintype "passive"))
      (node (ref "U6") (pin "2") (pinfunction "PC13_2") (pintype "bidirectional"))
    )
    (net (code "61") (name "Net-(U6-PC14)") (class "Default")
      (node (ref "R31") (pin "2") (pinfunction "2_2") (pintype "passive"))
      (node (ref "U6") (pin "3") (pinfunction "PC14_3") (pintype "bidirectional"))
    )
    (net (code "62") (name "Net-(U7-SET)") (class "Default")
      (node (ref "R50") (pin "2") (pinfunction "2_2") (pintype "passive"))
      (node (ref "U7") (pin "5") (pinfunction "SET_5") (pintype "passive"))
    )
    (net (code "63") (name "Net-(U9-BYPASS)") (class "Default")
      (node (ref "C36") (pin "1") (pinfunction "1_1") (pintype "passive"))
      (node (ref "U9") (pin "4") (pinfunction "BYPASS_4") (pintype "passive"))
    )
    (net (code "64") (name "Net-(U11-A1)") (class "Default")
      (node (ref "R54") (pin "1") (pinfunction "1_1") (pintype "passive"))
      (node (ref "R55") (pin "2") (pinfunction "2_2") (pintype "passive"))
      (node (ref "U11") (pin "2") (pinfunction "A1_2") (pintype "passive"))
    )
    (net (code "65") (name "Net-(U11-A2)") (class "Default")
      (node (ref "R53") (pin "1") (pinfunction "1_1") (pintype "passive"))
      (node (ref "U11") (pin "3") (pinfunction "A2_3") (pintype "passive"))
    )
    (net (code "66") (name "U5V_ST_LINK") (class "Default")
      (node (ref "C29") (pin "2") (pinfunction "2_2") (pintype "passive"))
      (node (ref "U7") (pin "6") (pinfunction "OUT_6") (pintype "passive"))
      (node (ref "U7") (pin "7") (pinfunction "OUT_7") (pintype "passive"))
    )
    (net (code "67") (name "VDD") (class "Default")
      (node (ref "CN4") (pin "1") (pinfunction "1_1") (pintype "passive"))
      (node (ref "SW1") (pin "5") (pinfunction "5_5") (pintype "passive"))
    )
    (net (code "68") (name "VDD_STL") (class "Default")
      (node (ref "C34") (pin "1") (pinfunction "1_1") (pintype "passive"))
      (node (ref "C46") (pin "1") (pinfunction "1_1") (pintype "passive"))
      (node (ref "JP6") (pin "2") (pintype "passive"))
      (node (ref "R45") (pin "2") (pinfunction "2_2") (pintype "passive"))
      (node (ref "R53") (pin "2") (pinfunction "2_2") (pintype "passive"))
      (node (ref "R54") (pin "2") (pinfunction "2_2") (pintype "passive"))
      (node (ref "U11") (pin "1") (pinfunction "VCCA_1") (pintype "passive"))
      (node (ref "U11") (pin "5") (pinfunction "DIR_5") (pintype "passive"))
      (node (ref "U8") (pin "8") (pinfunction "VccB_8") (pintype "passive"))
    )
    (net (code "69") (name "unconnected-(CN4-Pad7)") (class "Default")
      (node (ref "CN4") (pin "7") (pinfunction "7_7") (pintype "passive+no_connect"))
    )
    (net (code "70") (name "unconnected-(CN4-Pad8)") (class "Default")
      (node (ref "CN4") (pin "8") (pinfunction "8_8") (pintype "passive+no_connect"))
    )
    (net (code "71") (name "unconnected-(CN4-Pad9)") (class "Default")
      (node (ref "CN4") (pin "9") (pinfunction "9_9") (pintype "passive+no_connect"))
    )
    (net (code "72") (name "unconnected-(U6-JNRST-Pad40)") (class "Default")
      (node (ref "U6") (pin "40") (pinfunction "JNRST_40") (pintype "bidirectional+no_connect"))
    )
    (net (code "73") (name "unconnected-(U6-PA1-Pad11)") (class "Default")
      (node (ref "U6") (pin "11") (pinfunction "PA1_11") (pintype "bidirectional+no_connect"))
    )
    (net (code "74") (name "unconnected-(U6-PB5-Pad41)") (class "Default")
      (node (ref "U6") (pin "41") (pinfunction "PB5_41") (pintype "bidirectional+no_connect"))
    )
    (net (code "75") (name "unconnected-(U6-PB6-Pad42)") (class "Default")
      (node (ref "U6") (pin "42") (pinfunction "PB6_42") (pintype "bidirectional+no_connect"))
    )
    (net (code "76") (name "unconnected-(U6-PB7-Pad43)") (class "Default")
      (node (ref "U6") (pin "43") (pinfunction "PB7_43") (pintype "bidirectional+no_connect"))
    )
    (net (code "77") (name "unconnected-(U6-PB8-Pad45)") (class "Default")
      (node (ref "U6") (pin "45") (pinfunction "PB8_45") (pintype "bidirectional+no_connect"))
    )
    (net (code "78") (name "unconnected-(U6-PB9-Pad46)") (class "Default")
      (node (ref "U6") (pin "46") (pinfunction "PB9_46") (pintype "bidirectional+no_connect"))
    )
    (net (code "79") (name "unconnected-(U6-PB10-Pad21)") (class "Default")
      (node (ref "U6") (pin "21") (pinfunction "PB10_21") (pintype "bidirectional+no_connect"))
    )
    (net (code "80") (name "unconnected-(U6-PB11-Pad22)") (class "Default")
      (node (ref "U6") (pin "22") (pinfunction "PB11_22") (pintype "passive+no_connect"))
    )
    (net (code "81") (name "unconnected-(U6-PC15-Pad4)") (class "Default")
      (node (ref "U6") (pin "4") (pinfunction "PC15_4") (pintype "bidirectional+no_connect"))
    )
    (net (code "82") (name "unconnected-(U6-U2_CK-Pad14)") (class "Default")
      (node (ref "U6") (pin "14") (pinfunction "U2_CK_14") (pintype "bidirectional+no_connect"))
    )
    (net (code "83") (name "unconnected-(U11-B2-Pad6)") (class "Default")
      (node (ref "U11") (pin "6") (pinfunction "B2_6") (pintype "passive+no_connect"))
    )
  )
)
